# AST1030.net
KiCad netlist of a schematic drawn in EAGLE
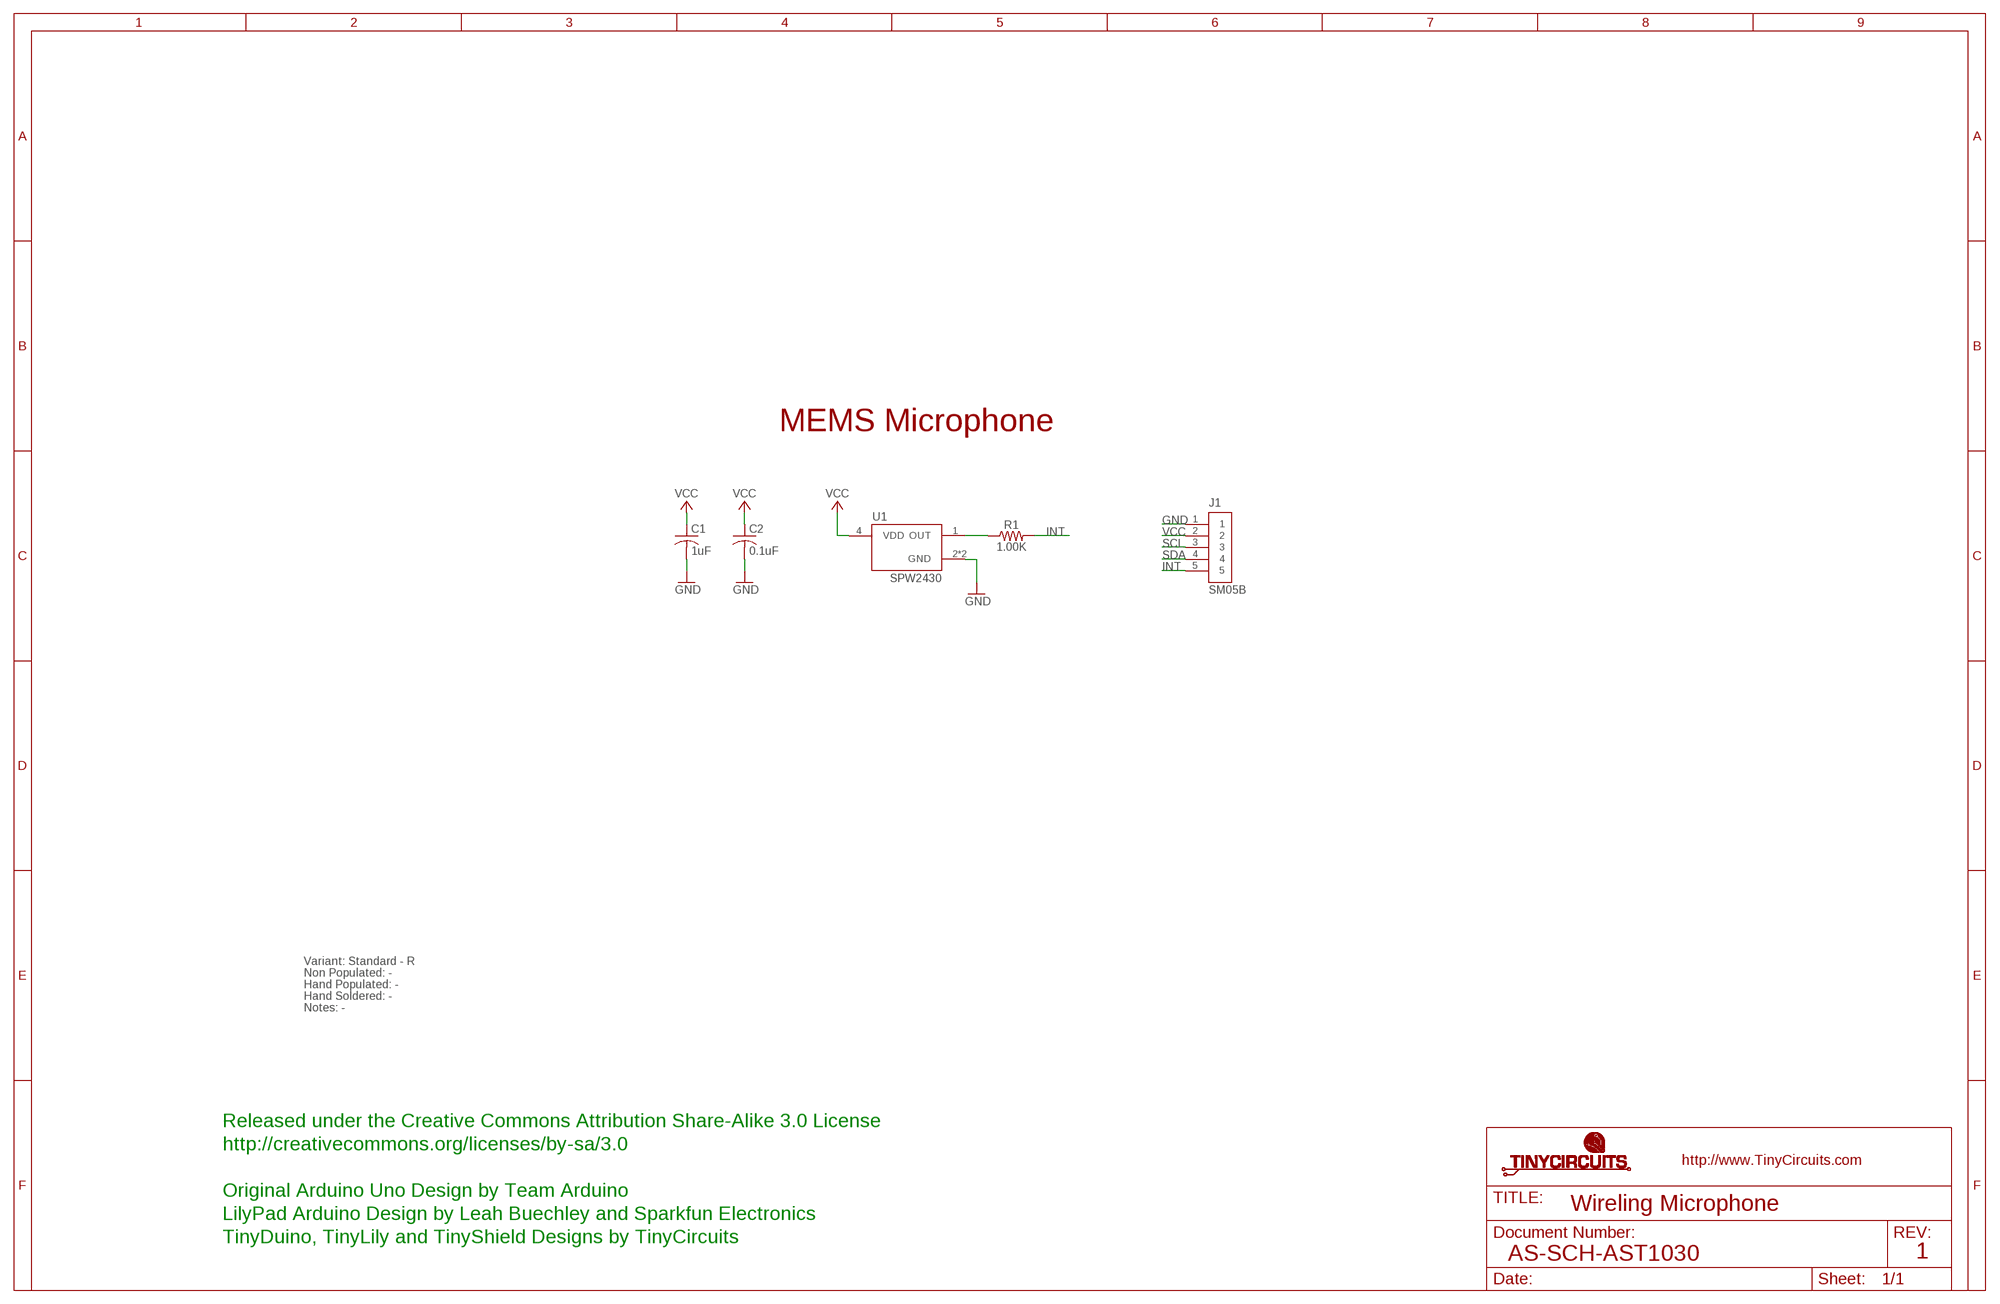
[diagram p0: schematic, sheet 1]

(export (version "E")
  (design (tool "Eeschema 10.0.6"))
  (components
    (comp (ref "C1")
      (value "1uF")
      (footprint "eagle-import:C0603")
      (fields (field (name "PARTNO") "AS-ITM-00410") (field (name "PARTNO_1") "AS-ITM-00410"))
      (libsource (lib "eagle-import") (part "AS-ITM-00410"))
    )
    (comp (ref "C2")
      (value "0.1uF")
      (footprint "eagle-import:C0402")
      (fields (field (name "PARTNO") "AS-ITM-00008"))
      (libsource (lib "eagle-import") (part "AS-ITM-00008"))
    )
    (comp (ref "J1")
      (value "SM05B")
      (footprint "eagle-import:JST_SH_5X1_EDGE")
      (fields (field (name "PARTNO") "AS-ITM-00340"))
      (libsource (lib "eagle-import") (part "AS-ITM-00340EDGE"))
    )
    (comp (ref "R1")
      (value "1.00K")
      (footprint "eagle-import:0402")
      (fields (field (name "PARTNO") "AS-ITM-00003"))
      (libsource (lib "eagle-import") (part "AS-ITM-00003"))
    )
    (comp (ref "U1")
      (value "SPW2430")
      (footprint "eagle-import:SPW2430HR5H-B")
      (fields (field (name "PARTNO") "AS-ITM-00387"))
      (libsource (lib "eagle-import") (part "AS-ITM-00387"))
    )
  )
  (nets
    (net (code "1") (name "/INT") (class "Default")
      (node (ref "J1") (pin "5") (pinfunction "5_5") (pintype "bidirectional"))
      (node (ref "R1") (pin "2") (pinfunction "2_2") (pintype "passive"))
    )
    (net (code "2") (name "/SCL") (class "Default")
      (node (ref "J1") (pin "3") (pinfunction "3_3") (pintype "bidirectional"))
    )
    (net (code "3") (name "/SDA") (class "Default")
      (node (ref "J1") (pin "4") (pinfunction "4_4") (pintype "bidirectional"))
    )
    (net (code "4") (name "GND") (class "Default")
      (node (ref "C1") (pin "2") (pinfunction "2_2") (pintype "passive"))
      (node (ref "C2") (pin "2") (pinfunction "2_2") (pintype "passive"))
      (node (ref "J1") (pin "1") (pinfunction "1_1") (pintype "bidirectional"))
      (node (ref "U1") (pin "2") (pinfunction "GND_2") (pintype "bidirectional"))
      (node (ref "U1") (pin "3") (pinfunction "GND_3") (pintype "bidirectional"))
    )
    (net (code "5") (name "Net-(U1-OUT)") (class "Default")
      (node (ref "R1") (pin "1") (pinfunction "1_1") (pintype "passive"))
      (node (ref "U1") (pin "1") (pinfunction "OUT_1") (pintype "bidirectional"))
    )
    (net (code "6") (name "VCC") (class "Default")
      (node (ref "C1") (pin "1") (pinfunction "1_1") (pintype "passive"))
      (node (ref "C2") (pin "1") (pinfunction "1_1") (pintype "passive"))
      (node (ref "J1") (pin "2") (pinfunction "2_2") (pintype "bidirectional"))
      (node (ref "U1") (pin "4") (pinfunction "VDD_4") (pintype "bidirectional"))
    )
  )
)
